# 5V_board.net
KiCad netlist of a schematic drawn in Altium Designer
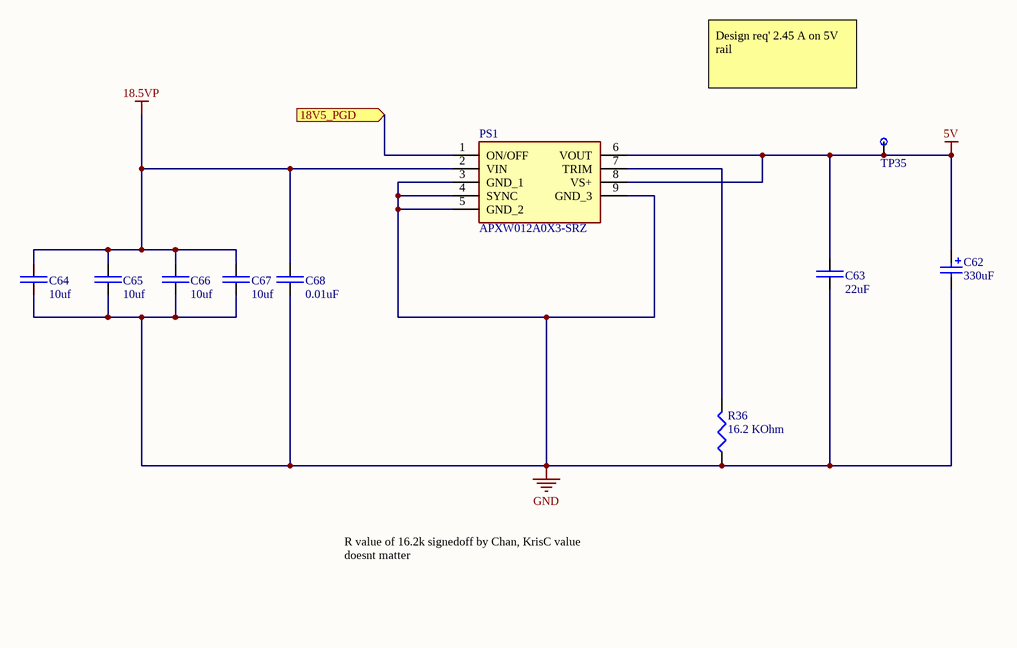
[diagram p0: 5V_board.SchDoc]

(export (version "E")
  (design (tool "Eeschema 10.0.6"))
  (components
    (comp (ref "C62")
      (value "330uF")
      (footprint "330uF throught hole")
      (description "CAP ALUM 330UF 20% 35V RADIAL")
      (fields (field (name "TOLERANCE") "20%"))
      (libsource (lib "RSX_Capacitors") (part "35ZLH330MEFCT810X12.5"))
    )
    (comp (ref "C63")
      (value "22uF")
      (footprint "22uF Capacitor")
      (description "Cap Ceramic 22uF 25V X7R 10% SMD 1210 125C Embossed T/R")
      (fields (field (name "TOLERANCE") "10%") (field (name "VOLTAGE") "25V"))
      (libsource (lib "RSX_Capacitors") (part "GRM32ER71E226KE15L"))
    )
    (comp (ref "C64")
      (value "10uf")
      (footprint "10uF capacitor LPB")
      (description "CAP CER 10UF 50V X5R 1206")
      (fields (field (name "TOLERANCE") "20%"))
      (libsource (lib "RSX_Capacitors") (part "GRT31CR61H106ME01L"))
    )
    (comp (ref "C65")
      (value "10uf")
      (footprint "10uF capacitor LPB")
      (description "CAP CER 10UF 50V X5R 1206")
      (fields (field (name "TOLERANCE") "20%"))
      (libsource (lib "RSX_Capacitors") (part "GRT31CR61H106ME01L"))
    )
    (comp (ref "C66")
      (value "10uf")
      (footprint "10uF capacitor LPB")
      (description "CAP CER 10UF 50V X5R 1206")
      (fields (field (name "TOLERANCE") "20%"))
      (libsource (lib "RSX_Capacitors") (part "GRT31CR61H106ME01L"))
    )
    (comp (ref "C67")
      (value "10uf")
      (footprint "10uF capacitor LPB")
      (description "CAP CER 10UF 50V X5R 1206")
      (fields (field (name "TOLERANCE") "20%"))
      (libsource (lib "RSX_Capacitors") (part "GRT31CR61H106ME01L"))
    )
    (comp (ref "C68")
      (value "0.01uF")
      (footprint "0.01uF capacitor")
      (description "Cap Ceramic 0.01uF 250V X7R 10% Pad SMD 0603 125C Automotive T/R")
      (fields (field (name "TOLERANCE") "10%"))
      (libsource (lib "RSX_Capacitors") (part "C0603C103KARACAUTO"))
    )
    (comp (ref "PS1")
      (value "APXW012A0X3-SRZ")
      (footprint "SamacSys:APXW012A0X3SRZ")
      (description "Power Supply")
      (fields (field (name "MOUSER PART NUMBER") "894-APXW012A0X3-SRZ"))
      (libsource (lib "SamacSys") (part "APXW012A0X3-SRZ"))
    )
    (comp (ref "R36")
      (value "16.2 KOhm")
      (footprint "16.2 KOhm Resistor")
      (description "RES SMD 16.2KOHM 0.5% 1/10W 0603")
      (fields (field (name "TOLERANCE") "0.5%"))
      (libsource (lib "RSX_Resistors") (part "RT0603DRD0716K2L"))
    )
    (comp (ref "TP35")
      (value "TestPt")
      (footprint "50_MIL_PAD")
      (libsource (lib "RSX_Test_Points") (part "TestPt"))
    )
  )
  (nets
    (net (code "1") (name "/18V5_PGD") (class "Default")
      (node (ref "PS1") (pin "1") (pinfunction "ON/OFF_1") (pintype "passive"))
    )
    (net (code "2") (name "5V") (class "Default")
      (node (ref "C62") (pin "1") (pinfunction "1_1") (pintype "passive"))
      (node (ref "C63") (pin "2") (pinfunction "16_2") (pintype "passive"))
      (node (ref "PS1") (pin "6") (pinfunction "VOUT_6") (pintype "passive"))
      (node (ref "PS1") (pin "8") (pinfunction "VS+_8") (pintype "passive"))
      (node (ref "TP35") (pin "1") (pinfunction "1_1") (pintype "passive"))
    )
    (net (code "3") (name "18.5VP") (class "Default")
      (node (ref "C64") (pin "2") (pinfunction "16_2") (pintype "passive"))
      (node (ref "C65") (pin "2") (pinfunction "16_2") (pintype "passive"))
      (node (ref "C66") (pin "2") (pinfunction "16_2") (pintype "passive"))
      (node (ref "C67") (pin "2") (pinfunction "16_2") (pintype "passive"))
      (node (ref "C68") (pin "2") (pinfunction "16_2") (pintype "passive"))
      (node (ref "PS1") (pin "2") (pinfunction "VIN_2") (pintype "passive"))
    )
    (net (code "4") (name "GND") (class "Default")
      (node (ref "C62") (pin "2") (pinfunction "2_2") (pintype "passive"))
      (node (ref "C63") (pin "1") (pinfunction "15_1") (pintype "passive"))
      (node (ref "C64") (pin "1") (pinfunction "15_1") (pintype "passive"))
      (node (ref "C65") (pin "1") (pinfunction "15_1") (pintype "passive"))
      (node (ref "C66") (pin "1") (pinfunction "15_1") (pintype "passive"))
      (node (ref "C67") (pin "1") (pinfunction "15_1") (pintype "passive"))
      (node (ref "C68") (pin "1") (pinfunction "15_1") (pintype "passive"))
      (node (ref "PS1") (pin "3") (pinfunction "GND_1_3") (pintype "passive"))
      (node (ref "PS1") (pin "4") (pinfunction "SYNC_4") (pintype "passive"))
      (node (ref "PS1") (pin "5") (pinfunction "GND_2_5") (pintype "passive"))
      (node (ref "PS1") (pin "9") (pinfunction "GND_3_9") (pintype "passive"))
      (node (ref "R36") (pin "1") (pinfunction "11_1") (pintype "passive"))
    )
    (net (code "5") (name "Net-(PS1-TRIM)") (class "Default")
      (node (ref "PS1") (pin "7") (pinfunction "TRIM_7") (pintype "passive"))
      (node (ref "R36") (pin "2") (pinfunction "12_2") (pintype "passive"))
    )
  )
)
